# sensorBoard.net
KiCad netlist of a schematic drawn in EAGLE
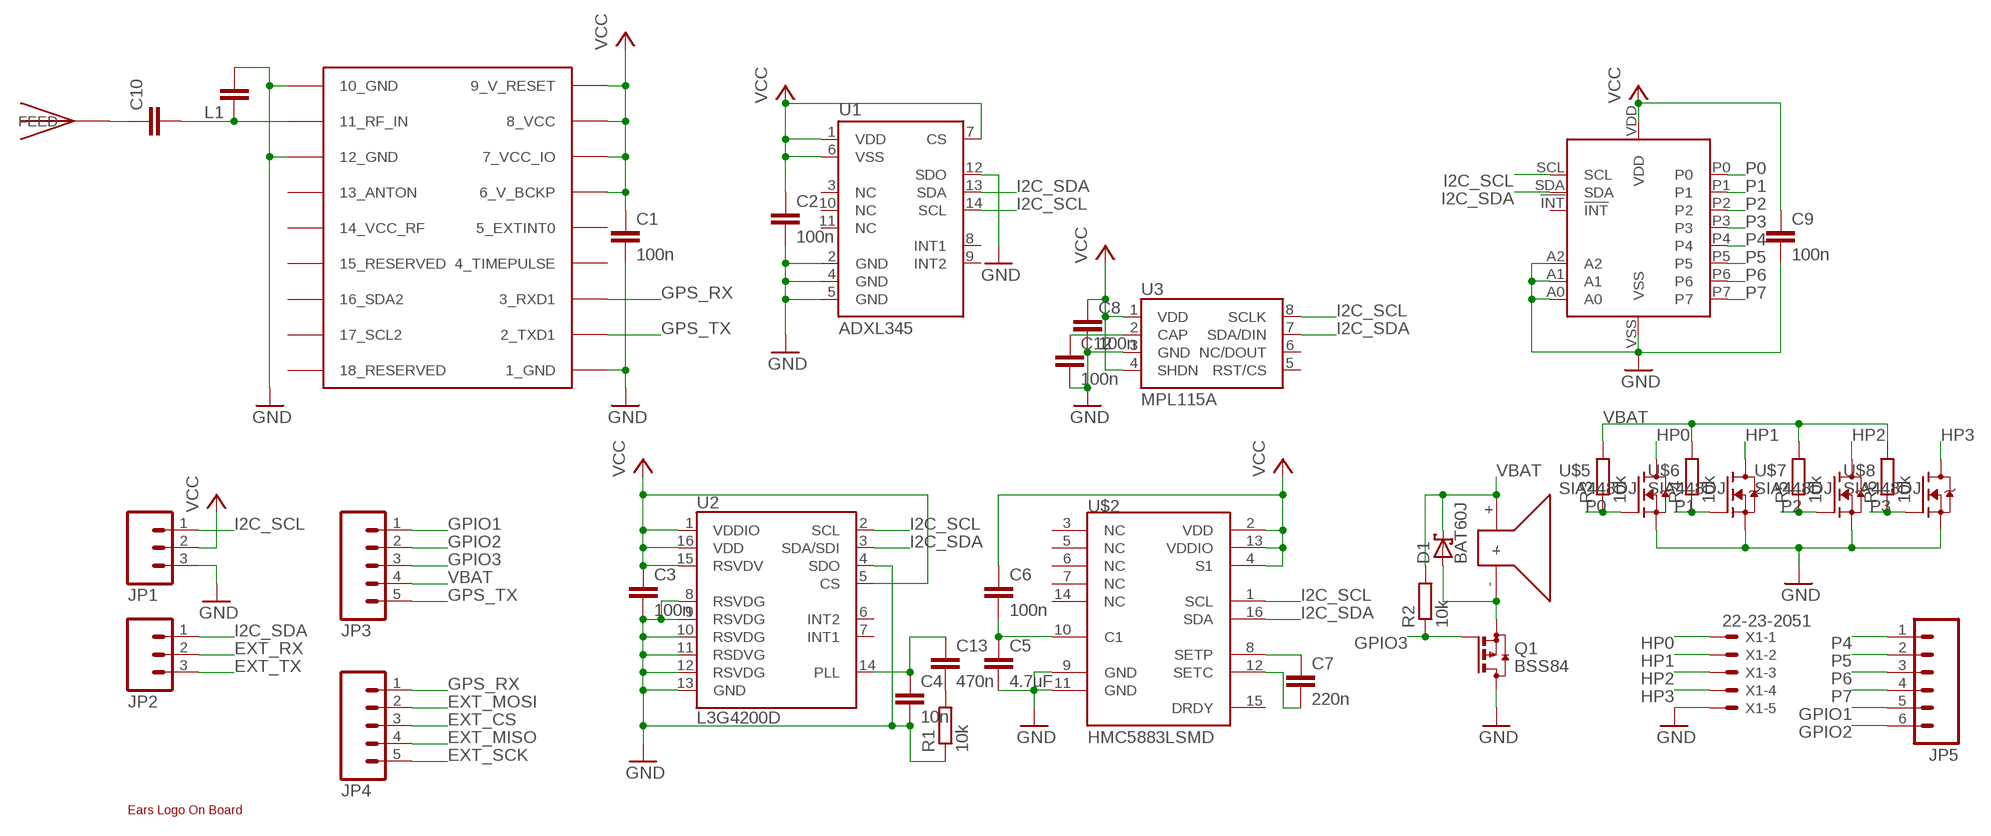
[diagram p0: schematic, sheet 1]

(export (version "E")
  (design (tool "Eeschema 10.0.6"))
  (components
    (comp (ref "C1")
      (value "100n")
      (footprint "eagle-import:C0402")
      (libsource (lib "eagle-import") (part "C-EUC0402"))
    )
    (comp (ref "C2")
      (value "100n")
      (footprint "eagle-import:C0402")
      (libsource (lib "eagle-import") (part "C-EUC0402"))
    )
    (comp (ref "C3")
      (value "100n")
      (footprint "eagle-import:C0402")
      (libsource (lib "eagle-import") (part "C-EUC0402"))
    )
    (comp (ref "C4")
      (value "10n")
      (footprint "eagle-import:C0402")
      (libsource (lib "eagle-import") (part "C-EUC0402"))
    )
    (comp (ref "C5")
      (value "4.7uF")
      (footprint "eagle-import:C0402")
      (libsource (lib "eagle-import") (part "C-EUC0402"))
    )
    (comp (ref "C6")
      (value "100n")
      (footprint "eagle-import:C0402")
      (libsource (lib "eagle-import") (part "C-EUC0402"))
    )
    (comp (ref "C7")
      (value "220n")
      (footprint "eagle-import:C0402")
      (libsource (lib "eagle-import") (part "C-EUC0402"))
    )
    (comp (ref "C8")
      (value "100n")
      (footprint "eagle-import:C0402")
      (libsource (lib "eagle-import") (part "C-EUC0402"))
    )
    (comp (ref "C9")
      (value "100n")
      (footprint "eagle-import:C0402")
      (libsource (lib "eagle-import") (part "C-EUC0402"))
    )
    (comp (ref "C10")
      (value "C-EUC0603")
      (footprint "eagle-import:C0603")
      (libsource (lib "eagle-import") (part "C-EUC0603"))
    )
    (comp (ref "C12")
      (value "100n")
      (footprint "eagle-import:C0402")
      (libsource (lib "eagle-import") (part "C-EUC0402"))
    )
    (comp (ref "C13")
      (value "470n")
      (footprint "eagle-import:C0402")
      (libsource (lib "eagle-import") (part "C-EUC0402"))
    )
    (comp (ref "D1")
      (value "BAT60J")
      (footprint "eagle-import:SOD323_ST")
      (libsource (lib "eagle-import") (part "BAT60J"))
    )
    (comp (ref "JP1")
      (value "M03PTH")
      (footprint "eagle-import:1X03")
      (libsource (lib "eagle-import") (part "M03PTH"))
    )
    (comp (ref "JP2")
      (value "M03PTH")
      (footprint "eagle-import:1X03")
      (libsource (lib "eagle-import") (part "M03PTH"))
    )
    (comp (ref "JP3")
      (value "M05PTH")
      (footprint "eagle-import:1X05")
      (libsource (lib "eagle-import") (part "M05PTH"))
    )
    (comp (ref "JP4")
      (value "M05PTH")
      (footprint "eagle-import:1X05")
      (libsource (lib "eagle-import") (part "M05PTH"))
    )
    (comp (ref "JP5")
      (value "M06SIP")
      (footprint "eagle-import:1X06")
      (libsource (lib "eagle-import") (part "M06SIP"))
    )
    (comp (ref "L1")
      (value "C-EUC0603")
      (footprint "eagle-import:C0603")
      (libsource (lib "eagle-import") (part "C-EUC0603"))
    )
    (comp (ref "Q1")
      (value "BSS84")
      (footprint "eagle-import:SOT23")
      (libsource (lib "eagle-import") (part "BSS84"))
    )
    (comp (ref "R1")
      (value "10k")
      (footprint "eagle-import:R0402")
      (libsource (lib "eagle-import") (part "R-EU_R0402"))
    )
    (comp (ref "R2")
      (value "10k")
      (footprint "eagle-import:R0402")
      (libsource (lib "eagle-import") (part "R-EU_R0402"))
    )
    (comp (ref "R3")
      (value "10k")
      (footprint "eagle-import:R0402")
      (libsource (lib "eagle-import") (part "R-EU_R0402"))
    )
    (comp (ref "R4")
      (value "10k")
      (footprint "eagle-import:R0402")
      (libsource (lib "eagle-import") (part "R-EU_R0402"))
    )
    (comp (ref "R5")
      (value "10k")
      (footprint "eagle-import:R0402")
      (libsource (lib "eagle-import") (part "R-EU_R0402"))
    )
    (comp (ref "R6")
      (value "10k")
      (footprint "eagle-import:R0402")
      (libsource (lib "eagle-import") (part "R-EU_R0402"))
    )
    (comp (ref "U$1")
      (value "UBLOX_MAX")
      (footprint "eagle-import:UBLOX_MAX")
      (libsource (lib "eagle-import") (part "UBLOX_MAX"))
    )
    (comp (ref "U$2")
      (value "HMC5883LSMD")
      (footprint "eagle-import:16LPCC")
      (libsource (lib "eagle-import") (part "HMC5883LSMD"))
    )
    (comp (ref "U$3")
      (value "KSSG23J12")
      (footprint "eagle-import:KSSG23J12")
      (libsource (lib "eagle-import") (part "KSSG23J12"))
    )
    (comp (ref "U$4")
      (value "PCAL9554B")
      (footprint "eagle-import:PCAL9554B")
      (libsource (lib "eagle-import") (part "PCAL9554B"))
    )
    (comp (ref "U$5")
      (value "SIA448DJ")
      (footprint "eagle-import:SIA448DJ")
      (libsource (lib "eagle-import") (part "SIA448DJ"))
    )
    (comp (ref "U$6")
      (value "SIA448DJ")
      (footprint "eagle-import:SIA448DJ")
      (libsource (lib "eagle-import") (part "SIA448DJ"))
    )
    (comp (ref "U$7")
      (value "SIA448DJ")
      (footprint "eagle-import:SIA448DJ")
      (libsource (lib "eagle-import") (part "SIA448DJ"))
    )
    (comp (ref "U$8")
      (value "SIA448DJ")
      (footprint "eagle-import:SIA448DJ")
      (libsource (lib "eagle-import") (part "SIA448DJ"))
    )
    (comp (ref "U$9")
      (value "JTI_ANTENNA-1575AT43A40")
      (footprint "eagle-import:JTI_ANTENNA-1575AT43A40")
      (libsource (lib "eagle-import") (part "JTI_ANTENNA-1575AT43A40"))
    )
    (comp (ref "U$10")
      (value "EARS-LOGO")
      (footprint "eagle-import:EARS-LOGO")
      (libsource (lib "eagle-import") (part "EARS-LOGO"))
    )
    (comp (ref "U1")
      (value "ADXL345")
      (footprint "eagle-import:LGA14")
      (libsource (lib "eagle-import") (part "ADXL345"))
    )
    (comp (ref "U2")
      (value "L3G4200D")
      (footprint "eagle-import:LGA16-4X4")
      (libsource (lib "eagle-import") (part "L3G4200D"))
    )
    (comp (ref "U3")
      (value "MPL115A")
      (footprint "eagle-import:LGA8")
      (libsource (lib "eagle-import") (part "MPL115A"))
    )
    (comp (ref "X1")
      (value "22-23-2051")
      (footprint "eagle-import:22-23-2051")
      (fields (field (name "MF") "MOLEX"))
      (libsource (lib "eagle-import") (part "22-23-2051"))
    )
  )
  (nets
    (net (code "1") (name "/EXT_CS") (class "Default")
      (node (ref "JP4") (pin "3") (pinfunction "3_3") (pintype "passive"))
    )
    (net (code "2") (name "/EXT_MISO") (class "Default")
      (node (ref "JP4") (pin "4") (pinfunction "4_4") (pintype "passive"))
    )
    (net (code "3") (name "/EXT_MOSI") (class "Default")
      (node (ref "JP4") (pin "2") (pinfunction "2_2") (pintype "passive"))
    )
    (net (code "4") (name "/EXT_RX") (class "Default")
      (node (ref "JP2") (pin "2") (pinfunction "2_2") (pintype "passive"))
    )
    (net (code "5") (name "/EXT_SCK") (class "Default")
      (node (ref "JP4") (pin "5") (pinfunction "5_5") (pintype "passive"))
    )
    (net (code "6") (name "/EXT_TX") (class "Default")
      (node (ref "JP2") (pin "3") (pinfunction "3_3") (pintype "passive"))
    )
    (net (code "7") (name "/GPIO1") (class "Default")
      (node (ref "JP3") (pin "1") (pinfunction "1_1") (pintype "passive"))
      (node (ref "JP5") (pin "5") (pinfunction "5_5") (pintype "passive"))
    )
    (net (code "8") (name "/GPIO2") (class "Default")
      (node (ref "JP3") (pin "2") (pinfunction "2_2") (pintype "passive"))
      (node (ref "JP5") (pin "6") (pinfunction "6_6") (pintype "passive"))
    )
    (net (code "9") (name "/GPIO3") (class "Default")
      (node (ref "JP3") (pin "3") (pinfunction "3_3") (pintype "passive"))
      (node (ref "Q1") (pin "1") (pinfunction "G_1") (pintype "passive"))
      (node (ref "R2") (pin "1") (pinfunction "1_1") (pintype "passive"))
    )
    (net (code "10") (name "/GPS_RX") (class "Default")
      (node (ref "JP4") (pin "1") (pinfunction "1_1") (pintype "passive"))
      (node (ref "U$1") (pin "3_RXD1") (pinfunction "3_RXD1_3_RXD1") (pintype "bidirectional"))
    )
    (net (code "11") (name "/GPS_TX") (class "Default")
      (node (ref "JP3") (pin "5") (pinfunction "5_5") (pintype "passive"))
      (node (ref "U$1") (pin "2_TXD1") (pinfunction "2_TXD1_2_TXD1") (pintype "bidirectional"))
    )
    (net (code "12") (name "/HP0") (class "Default")
      (node (ref "U$5") (pin "D0") (pinfunction "D_D0") (pintype "passive"))
      (node (ref "U$5") (pin "D1") (pinfunction "D_D1") (pintype "passive"))
      (node (ref "U$5") (pin "D2") (pinfunction "D_D2") (pintype "passive"))
      (node (ref "U$5") (pin "D5") (pinfunction "D_D5") (pintype "passive"))
      (node (ref "U$5") (pin "D6") (pinfunction "D_D6") (pintype "passive"))
      (node (ref "X1") (pin "1") (pinfunction "S_1") (pintype "passive"))
    )
    (net (code "13") (name "/HP1") (class "Default")
      (node (ref "U$6") (pin "D0") (pinfunction "D_D0") (pintype "passive"))
      (node (ref "U$6") (pin "D1") (pinfunction "D_D1") (pintype "passive"))
      (node (ref "U$6") (pin "D2") (pinfunction "D_D2") (pintype "passive"))
      (node (ref "U$6") (pin "D5") (pinfunction "D_D5") (pintype "passive"))
      (node (ref "U$6") (pin "D6") (pinfunction "D_D6") (pintype "passive"))
      (node (ref "X1") (pin "2") (pinfunction "S_2") (pintype "passive"))
    )
    (net (code "14") (name "/HP2") (class "Default")
      (node (ref "U$7") (pin "D0") (pinfunction "D_D0") (pintype "passive"))
      (node (ref "U$7") (pin "D1") (pinfunction "D_D1") (pintype "passive"))
      (node (ref "U$7") (pin "D2") (pinfunction "D_D2") (pintype "passive"))
      (node (ref "U$7") (pin "D5") (pinfunction "D_D5") (pintype "passive"))
      (node (ref "U$7") (pin "D6") (pinfunction "D_D6") (pintype "passive"))
      (node (ref "X1") (pin "3") (pinfunction "S_3") (pintype "passive"))
    )
    (net (code "15") (name "/HP3") (class "Default")
      (node (ref "U$8") (pin "D0") (pinfunction "D_D0") (pintype "passive"))
      (node (ref "U$8") (pin "D1") (pinfunction "D_D1") (pintype "passive"))
      (node (ref "U$8") (pin "D2") (pinfunction "D_D2") (pintype "passive"))
      (node (ref "U$8") (pin "D5") (pinfunction "D_D5") (pintype "passive"))
      (node (ref "U$8") (pin "D6") (pinfunction "D_D6") (pintype "passive"))
      (node (ref "X1") (pin "4") (pinfunction "S_4") (pintype "passive"))
    )
    (net (code "16") (name "/I2C_SCL") (class "Default")
      (node (ref "JP1") (pin "1") (pinfunction "1_1") (pintype "passive"))
      (node (ref "U$2") (pin "1") (pinfunction "SCL_1") (pintype "bidirectional"))
      (node (ref "U$4") (pin "SCL") (pinfunction "SCL_SCL") (pintype "bidirectional"))
      (node (ref "U1") (pin "14") (pinfunction "SCL_14") (pintype "bidirectional"))
      (node (ref "U2") (pin "2") (pinfunction "SCL_2") (pintype "bidirectional"))
      (node (ref "U3") (pin "8") (pinfunction "SCLK_8") (pintype "bidirectional"))
    )
    (net (code "17") (name "/I2C_SDA") (class "Default")
      (node (ref "JP2") (pin "1") (pinfunction "1_1") (pintype "passive"))
      (node (ref "U$2") (pin "16") (pinfunction "SDA_16") (pintype "bidirectional"))
      (node (ref "U$4") (pin "SDA") (pinfunction "SDA_SDA") (pintype "bidirectional"))
      (node (ref "U1") (pin "13") (pinfunction "SDA_13") (pintype "bidirectional"))
      (node (ref "U2") (pin "3") (pinfunction "SDA/SDI_3") (pintype "bidirectional"))
      (node (ref "U3") (pin "7") (pinfunction "SDA/DIN_7") (pintype "bidirectional"))
    )
    (net (code "18") (name "/P0") (class "Default")
      (node (ref "R3") (pin "1") (pinfunction "1_1") (pintype "passive"))
      (node (ref "U$4") (pin "P0") (pinfunction "P0_P0") (pintype "bidirectional"))
      (node (ref "U$5") (pin "G3") (pinfunction "G_G3") (pintype "passive"))
    )
    (net (code "19") (name "/P1") (class "Default")
      (node (ref "R4") (pin "1") (pinfunction "1_1") (pintype "passive"))
      (node (ref "U$4") (pin "P1") (pinfunction "P1_P1") (pintype "bidirectional"))
      (node (ref "U$6") (pin "G3") (pinfunction "G_G3") (pintype "passive"))
    )
    (net (code "20") (name "/P2") (class "Default")
      (node (ref "R5") (pin "1") (pinfunction "1_1") (pintype "passive"))
      (node (ref "U$4") (pin "P2") (pinfunction "P2_P2") (pintype "bidirectional"))
      (node (ref "U$7") (pin "G3") (pinfunction "G_G3") (pintype "passive"))
    )
    (net (code "21") (name "/P3") (class "Default")
      (node (ref "R6") (pin "1") (pinfunction "1_1") (pintype "passive"))
      (node (ref "U$4") (pin "P3") (pinfunction "P3_P3") (pintype "bidirectional"))
      (node (ref "U$8") (pin "G3") (pinfunction "G_G3") (pintype "passive"))
    )
    (net (code "22") (name "/P4") (class "Default")
      (node (ref "JP5") (pin "1") (pinfunction "1_1") (pintype "passive"))
      (node (ref "U$4") (pin "P4") (pinfunction "P4_P4") (pintype "bidirectional"))
    )
    (net (code "23") (name "/P5") (class "Default")
      (node (ref "JP5") (pin "2") (pinfunction "2_2") (pintype "passive"))
      (node (ref "U$4") (pin "P5") (pinfunction "P5_P5") (pintype "bidirectional"))
    )
    (net (code "24") (name "/P6") (class "Default")
      (node (ref "JP5") (pin "3") (pinfunction "3_3") (pintype "passive"))
      (node (ref "U$4") (pin "P6") (pinfunction "P6_P6") (pintype "bidirectional"))
    )
    (net (code "25") (name "/P7") (class "Default")
      (node (ref "JP5") (pin "4") (pinfunction "4_4") (pintype "passive"))
      (node (ref "U$4") (pin "P7") (pinfunction "P7_P7") (pintype "bidirectional"))
    )
    (net (code "26") (name "/VBAT") (class "Default")
      (node (ref "D1") (pin "C") (pinfunction "C_C") (pintype "passive"))
      (node (ref "JP3") (pin "4") (pinfunction "4_4") (pintype "passive"))
      (node (ref "R2") (pin "2") (pinfunction "2_2") (pintype "passive"))
      (node (ref "R3") (pin "2") (pinfunction "2_2") (pintype "passive"))
      (node (ref "R4") (pin "2") (pinfunction "2_2") (pintype "passive"))
      (node (ref "R5") (pin "2") (pinfunction "2_2") (pintype "passive"))
      (node (ref "R6") (pin "2") (pinfunction "2_2") (pintype "passive"))
      (node (ref "U$3") (pin "+") (pinfunction "+_+") (pintype "bidirectional"))
    )
    (net (code "27") (name "GND") (class "Default")
      (node (ref "C1") (pin "2") (pinfunction "2_2") (pintype "passive"))
      (node (ref "C12") (pin "2") (pinfunction "2_2") (pintype "passive"))
      (node (ref "C2") (pin "2") (pinfunction "2_2") (pintype "passive"))
      (node (ref "C3") (pin "2") (pinfunction "2_2") (pintype "passive"))
      (node (ref "C4") (pin "2") (pinfunction "2_2") (pintype "passive"))
      (node (ref "C5") (pin "2") (pinfunction "2_2") (pintype "passive"))
      (node (ref "C8") (pin "2") (pinfunction "2_2") (pintype "passive"))
      (node (ref "C9") (pin "2") (pinfunction "2_2") (pintype "passive"))
      (node (ref "JP1") (pin "3") (pinfunction "3_3") (pintype "passive"))
      (node (ref "L1") (pin "2") (pinfunction "2_2") (pintype "passive"))
      (node (ref "Q1") (pin "3") (pinfunction "D_3") (pintype "passive"))
      (node (ref "R1") (pin "1") (pinfunction "1_1") (pintype "passive"))
      (node (ref "U$1") (pin "10_GND") (pinfunction "10_GND_10_GND") (pintype "power_in"))
      (node (ref "U$1") (pin "12_GND") (pinfunction "12_GND_12_GND") (pintype "power_in"))
      (node (ref "U$1") (pin "1_GND") (pinfunction "1_GND_1_GND") (pintype "power_in"))
      (node (ref "U$2") (pin "11") (pinfunction "GND_11") (pintype "bidirectional"))
      (node (ref "U$2") (pin "9") (pinfunction "GND_9") (pintype "bidirectional"))
      (node (ref "U$4") (pin "A0") (pinfunction "A0_A0") (pintype "bidirectional"))
      (node (ref "U$4") (pin "A1") (pinfunction "A1_A1") (pintype "bidirectional"))
      (node (ref "U$4") (pin "A2") (pinfunction "A2_A2") (pintype "bidirectional"))
      (node (ref "U$4") (pin "VSS") (pinfunction "VSS_VSS") (pintype "bidirectional"))
      (node (ref "U$5") (pin "S0") (pinfunction "S_S0") (pintype "passive"))
      (node (ref "U$5") (pin "S4") (pinfunction "S_S4") (pintype "passive"))
      (node (ref "U$6") (pin "S0") (pinfunction "S_S0") (pintype "passive"))
      (node (ref "U$6") (pin "S4") (pinfunction "S_S4") (pintype "passive"))
      (node (ref "U$7") (pin "S0") (pinfunction "S_S0") (pintype "passive"))
      (node (ref "U$7") (pin "S4") (pinfunction "S_S4") (pintype "passive"))
      (node (ref "U$8") (pin "S0") (pinfunction "S_S0") (pintype "passive"))
      (node (ref "U$8") (pin "S4") (pinfunction "S_S4") (pintype "passive"))
      (node (ref "U1") (pin "12") (pinfunction "SDO_12") (pintype "bidirectional"))
      (node (ref "U1") (pin "2") (pinfunction "GND_2") (pintype "bidirectional"))
      (node (ref "U1") (pin "4") (pinfunction "GND_4") (pintype "bidirectional"))
      (node (ref "U1") (pin "5") (pinfunction "GND_5") (pintype "bidirectional"))
      (node (ref "U2") (pin "10") (pinfunction "RSVDG_10") (pintype "bidirectional"))
      (node (ref "U2") (pin "11") (pinfunction "RSDVG_11") (pintype "bidirectional"))
      (node (ref "U2") (pin "12") (pinfunction "RSVDG_12") (pintype "bidirectional"))
      (node (ref "U2") (pin "13") (pinfunction "GND_13") (pintype "bidirectional"))
      (node (ref "U2") (pin "4") (pinfunction "SDO_4") (pintype "bidirectional"))
      (node (ref "U2") (pin "8") (pinfunction "RSVDG_8") (pintype "bidirectional"))
      (node (ref "U2") (pin "9") (pinfunction "RSVDG_9") (pintype "bidirectional"))
      (node (ref "U3") (pin "3") (pinfunction "GND_3") (pintype "bidirectional"))
      (node (ref "X1") (pin "5") (pinfunction "S_5") (pintype "passive"))
    )
    (net (code "28") (name "Net-(C10-Pad1)") (class "Default")
      (node (ref "C10") (pin "1") (pinfunction "1_1") (pintype "passive"))
      (node (ref "U$9") (pin "FEED") (pinfunction "FEED_FEED") (pintype "bidirectional"))
    )
    (net (code "29") (name "Net-(C10-Pad2)") (class "Default")
      (node (ref "C10") (pin "2") (pinfunction "2_2") (pintype "passive"))
      (node (ref "L1") (pin "1") (pinfunction "1_1") (pintype "passive"))
      (node (ref "U$1") (pin "11_RF_IN") (pinfunction "11_RF_IN_11_RF_IN") (pintype "bidirectional"))
    )
    (net (code "30") (name "Net-(C13-Pad2)") (class "Default")
      (node (ref "C13") (pin "2") (pinfunction "2_2") (pintype "passive"))
      (node (ref "R1") (pin "2") (pinfunction "2_2") (pintype "passive"))
    )
    (net (code "31") (name "Net-(Q1-S)") (class "Default")
      (node (ref "D1") (pin "A") (pinfunction "A_A") (pintype "passive"))
      (node (ref "Q1") (pin "2") (pinfunction "S_2") (pintype "passive"))
      (node (ref "U$3") (pin "-") (pinfunction "-_-") (pintype "bidirectional"))
    )
    (net (code "32") (name "Net-(U$2-C1)") (class "Default")
      (node (ref "C5") (pin "1") (pinfunction "1_1") (pintype "passive"))
      (node (ref "C6") (pin "2") (pinfunction "2_2") (pintype "passive"))
      (node (ref "U$2") (pin "10") (pinfunction "C1_10") (pintype "bidirectional"))
    )
    (net (code "33") (name "Net-(U$2-SETC)") (class "Default")
      (node (ref "C7") (pin "2") (pinfunction "2_2") (pintype "passive"))
      (node (ref "U$2") (pin "12") (pinfunction "SETC_12") (pintype "bidirectional"))
    )
    (net (code "34") (name "Net-(U$2-SETP)") (class "Default")
      (node (ref "C7") (pin "1") (pinfunction "1_1") (pintype "passive"))
      (node (ref "U$2") (pin "8") (pinfunction "SETP_8") (pintype "bidirectional"))
    )
    (net (code "35") (name "Net-(U2-PLL)") (class "Default")
      (node (ref "C13") (pin "1") (pinfunction "1_1") (pintype "passive"))
      (node (ref "C4") (pin "1") (pinfunction "1_1") (pintype "passive"))
      (node (ref "U2") (pin "14") (pinfunction "PLL_14") (pintype "bidirectional"))
    )
    (net (code "36") (name "Net-(U3-CAP)") (class "Default")
      (node (ref "C12") (pin "1") (pinfunction "1_1") (pintype "passive"))
      (node (ref "U3") (pin "2") (pinfunction "CAP_2") (pintype "bidirectional"))
    )
    (net (code "37") (name "VCC") (class "Default")
      (node (ref "C1") (pin "1") (pinfunction "1_1") (pintype "passive"))
      (node (ref "C2") (pin "1") (pinfunction "1_1") (pintype "passive"))
      (node (ref "C3") (pin "1") (pinfunction "1_1") (pintype "passive"))
      (node (ref "C6") (pin "1") (pinfunction "1_1") (pintype "passive"))
      (node (ref "C8") (pin "1") (pinfunction "1_1") (pintype "passive"))
      (node (ref "C9") (pin "1") (pinfunction "1_1") (pintype "passive"))
      (node (ref "JP1") (pin "2") (pinfunction "2_2") (pintype "passive"))
      (node (ref "U$1") (pin "6_V_BCKP") (pinfunction "6_V_BCKP_6_V_BCKP") (pintype "bidirectional"))
      (node (ref "U$1") (pin "7_VCC_IO") (pinfunction "7_VCC_IO_7_VCC_IO") (pintype "power_in"))
      (node (ref "U$1") (pin "8_VCC") (pinfunction "8_VCC_8_VCC") (pintype "power_in"))
      (node (ref "U$1") (pin "9_V_RESET") (pinfunction "9_V_RESET_9_V_RESET") (pintype "power_in"))
      (node (ref "U$2") (pin "13") (pinfunction "VDDIO_13") (pintype "bidirectional"))
      (node (ref "U$2") (pin "2") (pinfunction "VDD_2") (pintype "bidirectional"))
      (node (ref "U$2") (pin "4") (pinfunction "S1_4") (pintype "bidirectional"))
      (node (ref "U$4") (pin "VDD") (pinfunction "VDD_VDD") (pintype "bidirectional"))
      (node (ref "U1") (pin "1") (pinfunction "VDD_1") (pintype "bidirectional"))
      (node (ref "U1") (pin "6") (pinfunction "VSS_6") (pintype "bidirectional"))
      (node (ref "U1") (pin "7") (pinfunction "CS_7") (pintype "bidirectional"))
      (node (ref "U2") (pin "1") (pinfunction "VDDIO_1") (pintype "bidirectional"))
      (node (ref "U2") (pin "15") (pinfunction "RSVDV_15") (pintype "bidirectional"))
      (node (ref "U2") (pin "16") (pinfunction "VDD_16") (pintype "bidirectional"))
      (node (ref "U2") (pin "5") (pinfunction "CS_5") (pintype "bidirectional"))
      (node (ref "U3") (pin "1") (pinfunction "VDD_1") (pintype "bidirectional"))
      (node (ref "U3") (pin "4") (pinfunction "SHDN_4") (pintype "bidirectional"))
    )
    (net (code "38") (name "unconnected-(U$1-Pad4_TIMEPULSE)") (class "Default")
      (node (ref "U$1") (pin "4_TIMEPULSE") (pinfunction "4_TIMEPULSE_4_TIMEPULSE") (pintype "bidirectional"))
    )
    (net (code "39") (name "unconnected-(U$1-Pad5_EXTINT0)") (class "Default")
      (node (ref "U$1") (pin "5_EXTINT0") (pinfunction "5_EXTINT0_5_EXTINT0") (pintype "bidirectional"))
    )
    (net (code "40") (name "unconnected-(U$1-Pad13_ANTON)") (class "Default")
      (node (ref "U$1") (pin "13_ANTON") (pinfunction "13_ANTON_13_ANTON") (pintype "bidirectional"))
    )
    (net (code "41") (name "unconnected-(U$1-Pad14_VCC_RF)") (class "Default")
      (node (ref "U$1") (pin "14_VCC_RF") (pinfunction "14_VCC_RF_14_VCC_RF") (pintype "bidirectional"))
    )
    (net (code "42") (name "unconnected-(U$1-Pad15_RESERVED)") (class "Default")
      (node (ref "U$1") (pin "15_RESERVED") (pinfunction "15_RESERVED_15_RESERVED") (pintype "bidirectional"))
    )
    (net (code "43") (name "unconnected-(U$1-Pad16_SDA2)") (class "Default")
      (node (ref "U$1") (pin "16_SDA2") (pinfunction "16_SDA2_16_SDA2") (pintype "bidirectional"))
    )
    (net (code "44") (name "unconnected-(U$1-Pad17_SCL2)") (class "Default")
      (node (ref "U$1") (pin "17_SCL2") (pinfunction "17_SCL2_17_SCL2") (pintype "bidirectional"))
    )
    (net (code "45") (name "unconnected-(U$1-Pad18_RESERVED)") (class "Default")
      (node (ref "U$1") (pin "18_RESERVED") (pinfunction "18_RESERVED_18_RESERVED") (pintype "bidirectional"))
    )
    (net (code "46") (name "unconnected-(U$2-DRDY-Pad15)") (class "Default")
      (node (ref "U$2") (pin "15") (pinfunction "DRDY_15") (pintype "bidirectional"))
    )
    (net (code "47") (name "unconnected-(U$2-NC-Pad3)") (class "Default")
      (node (ref "U$2") (pin "3") (pinfunction "NC_3") (pintype "bidirectional"))
    )
    (net (code "48") (name "unconnected-(U$2-NC-Pad5)") (class "Default")
      (node (ref "U$2") (pin "5") (pinfunction "NC_5") (pintype "bidirectional"))
    )
    (net (code "49") (name "unconnected-(U$2-NC-Pad6)") (class "Default")
      (node (ref "U$2") (pin "6") (pinfunction "NC_6") (pintype "bidirectional"))
    )
    (net (code "50") (name "unconnected-(U$2-NC-Pad7)") (class "Default")
      (node (ref "U$2") (pin "7") (pinfunction "NC_7") (pintype "bidirectional"))
    )
    (net (code "51") (name "unconnected-(U$2-NC-Pad14)") (class "Default")
      (node (ref "U$2") (pin "14") (pinfunction "NC_14") (pintype "bidirectional"))
    )
    (net (code "52") (name "unconnected-(U$4-~{INT}-Pad!INT)") (class "Default")
      (node (ref "U$4") (pin "!INT") (pinfunction "~{INT}_!INT") (pintype "bidirectional"))
    )
    (net (code "53") (name "unconnected-(U1-INT1-Pad8)") (class "Default")
      (node (ref "U1") (pin "8") (pinfunction "INT1_8") (pintype "bidirectional"))
    )
    (net (code "54") (name "unconnected-(U1-INT2-Pad9)") (class "Default")
      (node (ref "U1") (pin "9") (pinfunction "INT2_9") (pintype "bidirectional"))
    )
    (net (code "55") (name "unconnected-(U1-NC-Pad3)") (class "Default")
      (node (ref "U1") (pin "3") (pinfunction "NC_3") (pintype "bidirectional"))
    )
    (net (code "56") (name "unconnected-(U1-NC-Pad10)") (class "Default")
      (node (ref "U1") (pin "10") (pinfunction "NC_10") (pintype "bidirectional"))
    )
    (net (code "57") (name "unconnected-(U1-NC-Pad11)") (class "Default")
      (node (ref "U1") (pin "11") (pinfunction "NC_11") (pintype "bidirectional"))
    )
    (net (code "58") (name "unconnected-(U2-INT1-Pad7)") (class "Default")
      (node (ref "U2") (pin "7") (pinfunction "INT1_7") (pintype "bidirectional"))
    )
    (net (code "59") (name "unconnected-(U2-INT2-Pad6)") (class "Default")
      (node (ref "U2") (pin "6") (pinfunction "INT2_6") (pintype "bidirectional"))
    )
    (net (code "60") (name "unconnected-(U3-NC{slash}DOUT-Pad6)") (class "Default")
      (node (ref "U3") (pin "6") (pinfunction "NC/DOUT_6") (pintype "bidirectional"))
    )
    (net (code "61") (name "unconnected-(U3-RST{slash}CS-Pad5)") (class "Default")
      (node (ref "U3") (pin "5") (pinfunction "RST/CS_5") (pintype "bidirectional"))
    )
  )
)
